# 6_-CH340C.net
KiCad netlist of a schematic drawn in Altium Designer
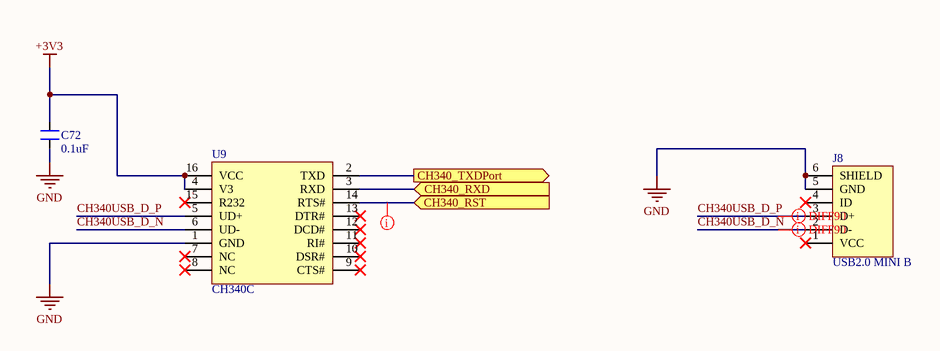
[diagram p0: (6)-CH340C.SchDoc]

(export (version "E")
  (design (tool "Eeschema 10.0.6"))
  (components
    (comp (ref "C72")
      (value "0.1uF")
      (footprint "CAP_0805")
      (description "0.1µF ±10% 50V Ceramic Capacitor X7R 0805 (2012 Metric)")
      (fields
        (field (name "MANUFACTURER") "Samsung")
        (field (name "MANUFACTURER PART NUMBER") "CL21B104KBCNNNC")
      )
      (libsource (lib "ESTEEMPCBLIB") (part "CAP_0.1uF-50V-10%-0805"))
    )
    (comp (ref "J8")
      (value "USB2.0 MINI B")
      (footprint "CON_690-005-299-043")
      (description "USB - mini B USB 2.0 Receptacle Connector 5 Position Surface Mount, Right Angle")
      (fields
        (field (name "MANUFACTURER") "EDAC")
        (field (name "MANUFACTURER PART NUMBER") "690-005-299-043")
      )
      (libsource (lib "ESTEEMPCBLIB") (part "CON_USB2.0-MINIB-SMD"))
    )
    (comp (ref "U9")
      (value "CH340C")
      (footprint "SOIC16_50_284_25X90_SMT")
      (description "USB Bridge, USB to UART USB 2.0 UART Interface")
      (fields (field (name "MANUFACTURER") "Olimex"))
      (libsource (lib "ESTEEMPCBLIB") (part "IC_CH340C"))
    )
  )
  (nets
    (net (code "1") (name "+3V3") (class "Default")
      (node (ref "C72") (pin "2") (pinfunction "2_2") (pintype "passive"))
      (node (ref "U9") (pin "16") (pinfunction "VCC_16") (pintype "passive"))
      (node (ref "U9") (pin "4") (pinfunction "V3_4") (pintype "passive"))
    )
    (net (code "2") (name "/CH340USB_D_N") (class "Default")
      (node (ref "J8") (pin "2") (pinfunction "D-_2") (pintype "passive"))
      (node (ref "U9") (pin "6") (pinfunction "UD-_6") (pintype "passive"))
    )
    (net (code "3") (name "/CH340USB_D_P") (class "Default")
      (node (ref "J8") (pin "3") (pinfunction "D+_3") (pintype "passive"))
      (node (ref "U9") (pin "5") (pinfunction "UD+_5") (pintype "passive"))
    )
    (net (code "4") (name "/CH340_RST") (class "Default")
      (node (ref "U9") (pin "14") (pinfunction "RTS#_14") (pintype "passive"))
    )
    (net (code "5") (name "/CH340_RXD") (class "Default")
      (node (ref "U9") (pin "3") (pinfunction "RXD_3") (pintype "passive"))
    )
    (net (code "6") (name "/CH340_TXDPort") (class "Default")
      (node (ref "U9") (pin "2") (pinfunction "TXD_2") (pintype "passive"))
    )
    (net (code "7") (name "GND") (class "Default")
      (node (ref "C72") (pin "1") (pinfunction "1_1") (pintype "passive"))
      (node (ref "J8") (pin "5") (pinfunction "GND_5") (pintype "passive"))
      (node (ref "J8") (pin "6") (pinfunction "SHIELD_6") (pintype "passive"))
      (node (ref "U9") (pin "1") (pinfunction "GND_1") (pintype "passive"))
    )
    (net (code "8") (name "unconnected-(J8-ID-Pad4)") (class "Default")
      (node (ref "J8") (pin "4") (pinfunction "ID_4") (pintype "passive+no_connect"))
    )
    (net (code "9") (name "unconnected-(J8-VCC-Pad1)") (class "Default")
      (node (ref "J8") (pin "1") (pinfunction "VCC_1") (pintype "passive+no_connect"))
    )
    (net (code "10") (name "unconnected-(U9-CTS#-Pad9)") (class "Default")
      (node (ref "U9") (pin "9") (pinfunction "CTS#_9") (pintype "passive+no_connect"))
    )
    (net (code "11") (name "unconnected-(U9-DCD#-Pad12)") (class "Default")
      (node (ref "U9") (pin "12") (pinfunction "DCD#_12") (pintype "passive+no_connect"))
    )
    (net (code "12") (name "unconnected-(U9-DSR#-Pad10)") (class "Default")
      (node (ref "U9") (pin "10") (pinfunction "DSR#_10") (pintype "passive+no_connect"))
    )
    (net (code "13") (name "unconnected-(U9-DTR#-Pad13)") (class "Default")
      (node (ref "U9") (pin "13") (pinfunction "DTR#_13") (pintype "passive+no_connect"))
    )
    (net (code "14") (name "unconnected-(U9-NC-Pad7)") (class "Default")
      (node (ref "U9") (pin "7") (pinfunction "NC_7") (pintype "passive+no_connect"))
    )
    (net (code "15") (name "unconnected-(U9-NC-Pad8)") (class "Default")
      (node (ref "U9") (pin "8") (pinfunction "NC_8") (pintype "passive+no_connect"))
    )
    (net (code "16") (name "unconnected-(U9-R232-Pad15)") (class "Default")
      (node (ref "U9") (pin "15") (pinfunction "R232_15") (pintype "passive+no_connect"))
    )
    (net (code "17") (name "unconnected-(U9-RI#-Pad11)") (class "Default")
      (node (ref "U9") (pin "11") (pinfunction "RI#_11") (pintype "passive+no_connect"))
    )
  )
)
